# schematic.net
KiCad netlist of a schematic drawn in Altium Designer
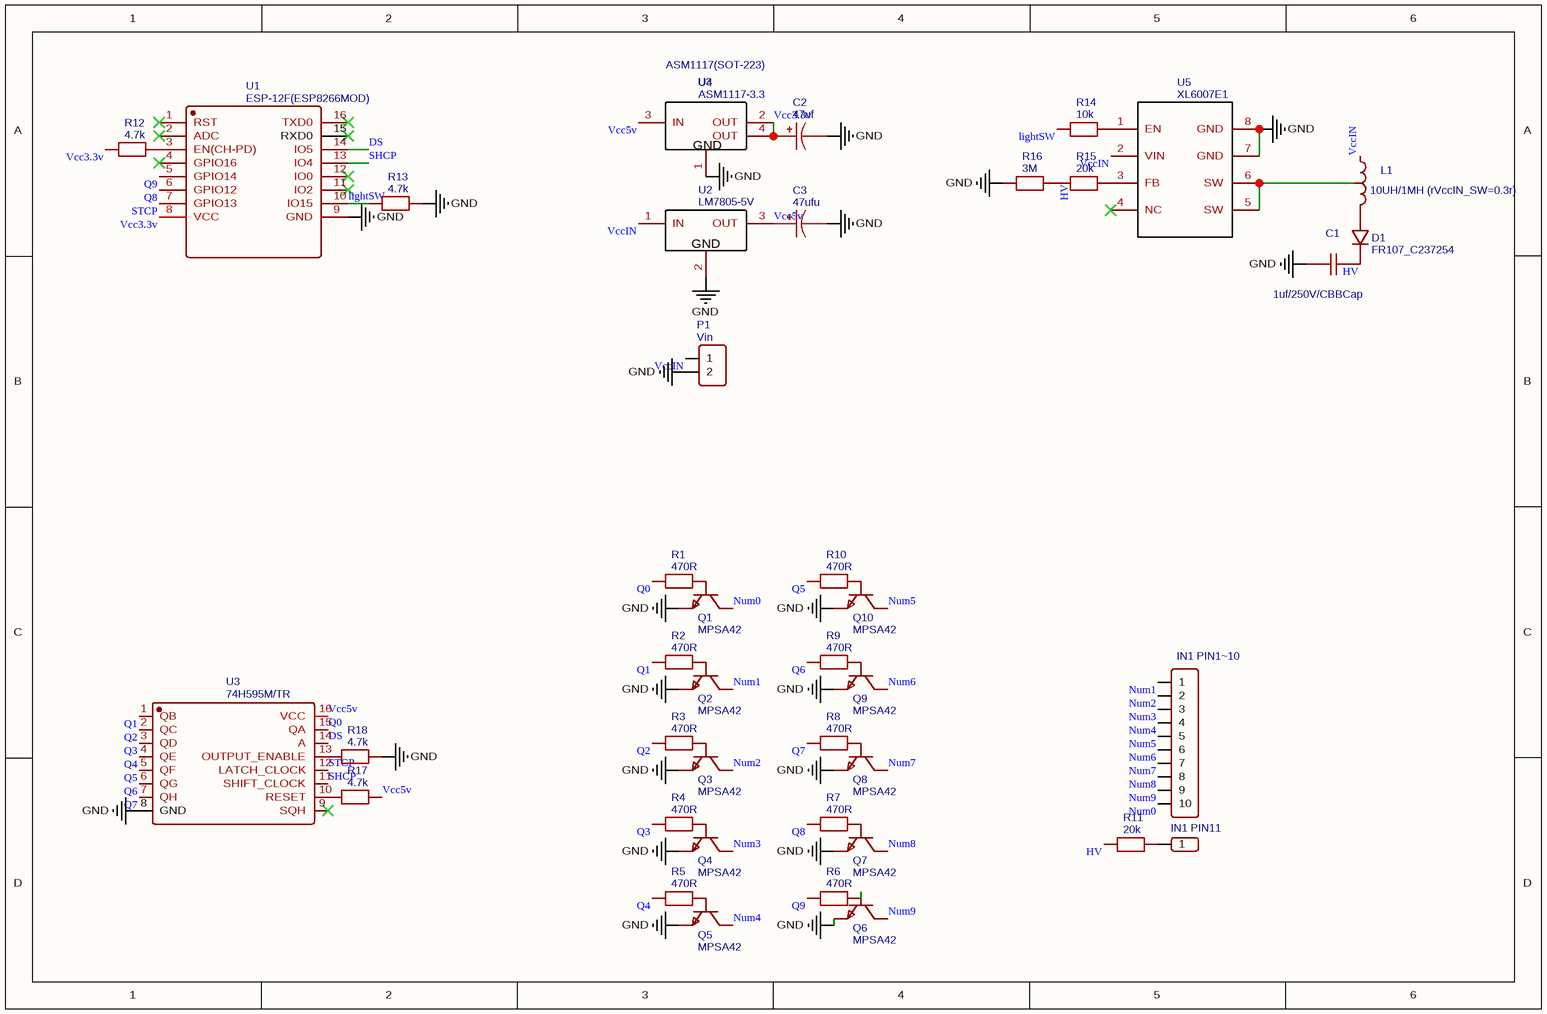
[diagram p0: schematic.schdoc]

(export (version "E")
  (design (tool "Eeschema 10.0.6"))
  (components
    (comp (ref "C1")
      (value "1uf/250V/CBBCap")
      (fields
        (field (name "BOM_SUPPLIER PART") "C29321")
        (field (name "BOM_MANUFACTURER PART") "1uf/250V/CBBCapacitor")
      )
      (libsource (lib "altium-import") (part "root_2_1uf/250V/CBBCap_"))
    )
    (comp (ref "C2")
      (value "47uf")
      (fields (field (name "CONTRIBUTOR") "LCEDA_Lib"))
      (libsource (lib "altium-import") (part "root_0_47uf_"))
    )
    (comp (ref "C3")
      (value "47ufu")
      (fields (field (name "CONTRIBUTOR") "LCEDA_Lib"))
      (libsource (lib "altium-import") (part "root_0_47ufu_"))
    )
    (comp (ref "D1")
      (value "FR107_C237254")
      (fields
        (field (name "BOM_SUPPLIER PART") "C237254")
        (field (name "BOM_MANUFACTURER PART") "FR107")
        (field (name "CONTRIBUTOR") "LCSC")
      )
      (libsource (lib "altium-import") (part "root_1_FR107_C237254_"))
    )
    (comp (ref "H1")
      (value "IN1 PIN1~10")
      (fields (field (name "BOM_SUPPLIER PART") "C35445") (field (name "CONTRIBUTOR") "LCEDA_Lib"))
      (libsource (lib "altium-import") (part "root_0_IN1 PIN1~10_"))
    )
    (comp (ref "J1")
      (value "IN1 PIN11")
      (fields (field (name "BOM_SUPPLIER PART") "C81276") (field (name "CONTRIBUTOR") "LCEDA_Lib"))
      (libsource (lib "altium-import") (part "root_0_IN1 PIN11_"))
    )
    (comp (ref "L1")
      (value "10UH/1MH (rVccIN_SW=0.3r)")
      (fields (field (name "CONTRIBUTOR") "NKB-NB"))
      (libsource (lib "altium-import") (part "root_0_10UH/1MH (rVccIN_SW=0.3r)_"))
    )
    (comp (ref "P1")
      (value "Vin")
      (fields (field (name "CONTRIBUTOR") "LCEDA_Lib"))
      (libsource (lib "altium-import") (part "root_0_Vin_"))
    )
    (comp (ref "Q1")
      (value "MPSA42")
      (fields (field (name "BOM_SUPPLIER PART") "C118557") (field (name "CONTRIBUTOR") "LCSC"))
      (libsource (lib "altium-import") (part "root_3_MPSA42_"))
    )
    (comp (ref "Q2")
      (value "MPSA42")
      (fields (field (name "BOM_SUPPLIER PART") "C118557") (field (name "CONTRIBUTOR") "LCSC"))
      (libsource (lib "altium-import") (part "root_3_MPSA42_"))
    )
    (comp (ref "Q3")
      (value "MPSA42")
      (fields (field (name "BOM_SUPPLIER PART") "C118557") (field (name "CONTRIBUTOR") "LCSC"))
      (libsource (lib "altium-import") (part "root_3_MPSA42_"))
    )
    (comp (ref "Q4")
      (value "MPSA42")
      (fields (field (name "BOM_SUPPLIER PART") "C118557") (field (name "CONTRIBUTOR") "LCSC"))
      (libsource (lib "altium-import") (part "root_3_MPSA42_"))
    )
    (comp (ref "Q5")
      (value "MPSA42")
      (fields (field (name "BOM_SUPPLIER PART") "C118557") (field (name "CONTRIBUTOR") "LCSC"))
      (libsource (lib "altium-import") (part "root_3_MPSA42_"))
    )
    (comp (ref "Q6")
      (value "MPSA42")
      (fields (field (name "BOM_SUPPLIER PART") "C118557") (field (name "CONTRIBUTOR") "LCSC"))
      (libsource (lib "altium-import") (part "root_3_MPSA42_"))
    )
    (comp (ref "Q7")
      (value "MPSA42")
      (fields (field (name "BOM_SUPPLIER PART") "C118557") (field (name "CONTRIBUTOR") "LCSC"))
      (libsource (lib "altium-import") (part "root_3_MPSA42_"))
    )
    (comp (ref "Q8")
      (value "MPSA42")
      (fields (field (name "BOM_SUPPLIER PART") "C118557") (field (name "CONTRIBUTOR") "LCSC"))
      (libsource (lib "altium-import") (part "root_3_MPSA42_"))
    )
    (comp (ref "Q9")
      (value "MPSA42")
      (fields (field (name "BOM_SUPPLIER PART") "C118557") (field (name "CONTRIBUTOR") "LCSC"))
      (libsource (lib "altium-import") (part "root_3_MPSA42_"))
    )
    (comp (ref "Q10")
      (value "MPSA42")
      (fields (field (name "BOM_SUPPLIER PART") "C118557") (field (name "CONTRIBUTOR") "LCSC"))
      (libsource (lib "altium-import") (part "root_3_MPSA42_"))
    )
    (comp (ref "R1")
      (value "470R")
      (fields (field (name "CONTRIBUTOR") "LCEDA_Lib"))
      (libsource (lib "altium-import") (part "root_2_470R_"))
    )
    (comp (ref "R2")
      (value "470R")
      (fields (field (name "CONTRIBUTOR") "LCEDA_Lib"))
      (libsource (lib "altium-import") (part "root_2_470R_"))
    )
    (comp (ref "R3")
      (value "470R")
      (fields (field (name "CONTRIBUTOR") "LCEDA_Lib"))
      (libsource (lib "altium-import") (part "root_2_470R_"))
    )
    (comp (ref "R4")
      (value "470R")
      (fields (field (name "CONTRIBUTOR") "LCEDA_Lib"))
      (libsource (lib "altium-import") (part "root_2_470R_"))
    )
    (comp (ref "R5")
      (value "470R")
      (fields (field (name "CONTRIBUTOR") "LCEDA_Lib"))
      (libsource (lib "altium-import") (part "root_2_470R_"))
    )
    (comp (ref "R6")
      (value "470R")
      (fields (field (name "CONTRIBUTOR") "LCEDA_Lib"))
      (libsource (lib "altium-import") (part "root_2_470R_"))
    )
    (comp (ref "R7")
      (value "470R")
      (fields (field (name "CONTRIBUTOR") "LCEDA_Lib"))
      (libsource (lib "altium-import") (part "root_2_470R_"))
    )
    (comp (ref "R8")
      (value "470R")
      (fields (field (name "CONTRIBUTOR") "LCEDA_Lib"))
      (libsource (lib "altium-import") (part "root_2_470R_"))
    )
    (comp (ref "R9")
      (value "470R")
      (fields (field (name "CONTRIBUTOR") "LCEDA_Lib"))
      (libsource (lib "altium-import") (part "root_2_470R_"))
    )
    (comp (ref "R10")
      (value "470R")
      (fields (field (name "CONTRIBUTOR") "LCEDA_Lib"))
      (libsource (lib "altium-import") (part "root_2_470R_"))
    )
    (comp (ref "R11")
      (value "20k")
      (fields (field (name "CONTRIBUTOR") "LCEDA_Lib"))
      (libsource (lib "altium-import") (part "root_0_20k_"))
    )
    (comp (ref "R12")
      (value "4.7k")
      (fields (field (name "CONTRIBUTOR") "LCEDA_Lib"))
      (libsource (lib "altium-import") (part "root_2_4.7k_"))
    )
    (comp (ref "R13")
      (value "4.7k")
      (fields (field (name "CONTRIBUTOR") "LCEDA_Lib"))
      (libsource (lib "altium-import") (part "root_0_4.7k_"))
    )
    (comp (ref "R14")
      (value "10k")
      (fields (field (name "CONTRIBUTOR") "LCEDA_Lib"))
      (libsource (lib "altium-import") (part "root_0_10k_"))
    )
    (comp (ref "R15")
      (value "20k")
      (fields (field (name "CONTRIBUTOR") "LCEDA_Lib"))
      (libsource (lib "altium-import") (part "root_0_20k_"))
    )
    (comp (ref "R16")
      (value "3M")
      (fields (field (name "CONTRIBUTOR") "LCEDA_Lib"))
      (libsource (lib "altium-import") (part "root_0_3M_"))
    )
    (comp (ref "R17")
      (value "4.7k")
      (fields (field (name "CONTRIBUTOR") "LCEDA_Lib"))
      (libsource (lib "altium-import") (part "root_0_4.7k_"))
    )
    (comp (ref "R18")
      (value "4.7k")
      (fields (field (name "CONTRIBUTOR") "LCEDA_Lib"))
      (libsource (lib "altium-import") (part "root_0_4.7k_"))
    )
    (comp (ref "U1")
      (value "ESP-12F(ESP8266MOD)")
      (fields (field (name "BOM_SUPPLIER PART") "C82891") (field (name "CONTRIBUTOR") "Diago"))
      (libsource (lib "altium-import") (part "root_0_ESP-12F(ESP8266MOD)_"))
    )
    (comp (ref "U2")
      (value "LM7805-5V")
      (fields (field (name "BOM_SUPPLIER PART") "C9900008050") (field (name "CONTRIBUTOR") "LCSC"))
      (libsource (lib "altium-import") (part "root_0_LM7805-5V_"))
    )
    (comp (ref "U3")
      (value "74H595M/TR")
      (fields (field (name "CONTRIBUTOR") "lianan"))
      (libsource (lib "altium-import") (part "root_0_74H595M/TR_"))
    )
    (comp (ref "U4")
      (value "ASM1117-3.3")
      (fields (field (name "CONTRIBUTOR") "shiznegjie"))
      (libsource (lib "altium-import") (part "root_0_ASM1117-3.3_"))
    )
    (comp (ref "U5")
      (value "XL6007E1")
      (fields (field (name "BOM_SUPPLIER PART") "C73334") (field (name "CONTRIBUTOR") "roco2022"))
      (libsource (lib "altium-import") (part "root_0_XL6007E1_"))
    )
  )
  (nets
    (net (code "1") (name "/DS") (class "Default")
      (node (ref "U1") (pin "14") (pinfunction "IO5_14") (pintype "passive"))
      (node (ref "U3") (pin "14") (pinfunction "A_14") (pintype "passive"))
    )
    (net (code "2") (name "/HV") (class "Default")
      (node (ref "C1") (pin "1") (pinfunction "1_1") (pintype "passive"))
      (node (ref "D1") (pin "1") (pinfunction "K_1") (pintype "passive"))
      (node (ref "R11") (pin "1") (pinfunction "1_1") (pintype "passive"))
      (node (ref "R15") (pin "1") (pinfunction "1_1") (pintype "passive"))
      (node (ref "R16") (pin "2") (pinfunction "2_2") (pintype "passive"))
    )
    (net (code "3") (name "/Num0") (class "Default")
      (node (ref "H1") (pin "10") (pinfunction "10_10") (pintype "passive"))
      (node (ref "Q1") (pin "3") (pinfunction "C_3") (pintype "passive"))
    )
    (net (code "4") (name "/Num1") (class "Default")
      (node (ref "H1") (pin "1") (pinfunction "1_1") (pintype "passive"))
      (node (ref "Q2") (pin "3") (pinfunction "C_3") (pintype "passive"))
    )
    (net (code "5") (name "/Num2") (class "Default")
      (node (ref "H1") (pin "2") (pinfunction "2_2") (pintype "passive"))
      (node (ref "Q3") (pin "3") (pinfunction "C_3") (pintype "passive"))
    )
    (net (code "6") (name "/Num3") (class "Default")
      (node (ref "H1") (pin "3") (pinfunction "3_3") (pintype "passive"))
      (node (ref "Q4") (pin "3") (pinfunction "C_3") (pintype "passive"))
    )
    (net (code "7") (name "/Num4") (class "Default")
      (node (ref "H1") (pin "4") (pinfunction "4_4") (pintype "passive"))
      (node (ref "Q5") (pin "3") (pinfunction "C_3") (pintype "passive"))
    )
    (net (code "8") (name "/Num5") (class "Default")
      (node (ref "H1") (pin "5") (pinfunction "5_5") (pintype "passive"))
      (node (ref "Q10") (pin "3") (pinfunction "C_3") (pintype "passive"))
    )
    (net (code "9") (name "/Num6") (class "Default")
      (node (ref "H1") (pin "6") (pinfunction "6_6") (pintype "passive"))
      (node (ref "Q9") (pin "3") (pinfunction "C_3") (pintype "passive"))
    )
    (net (code "10") (name "/Num7") (class "Default")
      (node (ref "H1") (pin "7") (pinfunction "7_7") (pintype "passive"))
      (node (ref "Q8") (pin "3") (pinfunction "C_3") (pintype "passive"))
    )
    (net (code "11") (name "/Num8") (class "Default")
      (node (ref "H1") (pin "8") (pinfunction "8_8") (pintype "passive"))
      (node (ref "Q7") (pin "3") (pinfunction "C_3") (pintype "passive"))
    )
    (net (code "12") (name "/Num9") (class "Default")
      (node (ref "H1") (pin "9") (pinfunction "9_9") (pintype "passive"))
      (node (ref "Q6") (pin "3") (pinfunction "C_3") (pintype "passive"))
    )
    (net (code "13") (name "/Q0") (class "Default")
      (node (ref "R1") (pin "2") (pinfunction "2_2") (pintype "passive"))
      (node (ref "U3") (pin "15") (pinfunction "QA_15") (pintype "passive"))
    )
    (net (code "14") (name "/Q1") (class "Default")
      (node (ref "R2") (pin "2") (pinfunction "2_2") (pintype "passive"))
      (node (ref "U3") (pin "1") (pinfunction "QB_1") (pintype "passive"))
    )
    (net (code "15") (name "/Q2") (class "Default")
      (node (ref "R3") (pin "2") (pinfunction "2_2") (pintype "passive"))
      (node (ref "U3") (pin "2") (pinfunction "QC_2") (pintype "passive"))
    )
    (net (code "16") (name "/Q3") (class "Default")
      (node (ref "R4") (pin "2") (pinfunction "2_2") (pintype "passive"))
      (node (ref "U3") (pin "3") (pinfunction "QD_3") (pintype "passive"))
    )
    (net (code "17") (name "/Q4") (class "Default")
      (node (ref "R5") (pin "2") (pinfunction "2_2") (pintype "passive"))
      (node (ref "U3") (pin "4") (pinfunction "QE_4") (pintype "passive"))
    )
    (net (code "18") (name "/Q5") (class "Default")
      (node (ref "R10") (pin "2") (pinfunction "2_2") (pintype "passive"))
      (node (ref "U3") (pin "5") (pinfunction "QF_5") (pintype "passive"))
    )
    (net (code "19") (name "/Q6") (class "Default")
      (node (ref "R9") (pin "2") (pinfunction "2_2") (pintype "passive"))
      (node (ref "U3") (pin "6") (pinfunction "QG_6") (pintype "passive"))
    )
    (net (code "20") (name "/Q7") (class "Default")
      (node (ref "R8") (pin "2") (pinfunction "2_2") (pintype "passive"))
      (node (ref "U3") (pin "7") (pinfunction "QH_7") (pintype "passive"))
    )
    (net (code "21") (name "/Q8") (class "Default")
      (node (ref "R7") (pin "2") (pinfunction "2_2") (pintype "passive"))
      (node (ref "U1") (pin "6") (pinfunction "GPIO12_6") (pintype "passive"))
    )
    (net (code "22") (name "/Q9") (class "Default")
      (node (ref "R6") (pin "2") (pinfunction "2_2") (pintype "passive"))
      (node (ref "U1") (pin "5") (pinfunction "GPIO14_5") (pintype "passive"))
    )
    (net (code "23") (name "/SHCP") (class "Default")
      (node (ref "U1") (pin "13") (pinfunction "IO4_13") (pintype "passive"))
      (node (ref "U3") (pin "11") (pinfunction "SHIFT_CLOCK_11") (pintype "passive"))
    )
    (net (code "24") (name "/STCP") (class "Default")
      (node (ref "U1") (pin "7") (pinfunction "GPIO13_7") (pintype "passive"))
      (node (ref "U3") (pin "12") (pinfunction "LATCH_CLOCK_12") (pintype "passive"))
    )
    (net (code "25") (name "/Vcc3.3v") (class "Default")
      (node (ref "C2") (pin "1") (pinfunction "1_1") (pintype "passive"))
      (node (ref "R12") (pin "2") (pinfunction "2_2") (pintype "passive"))
      (node (ref "U1") (pin "8") (pinfunction "VCC_8") (pintype "passive"))
      (node (ref "U4") (pin "2") (pinfunction "OUT_2") (pintype "passive"))
      (node (ref "U4") (pin "4") (pinfunction "OUT_4") (pintype "passive"))
    )
    (net (code "26") (name "/Vcc5v") (class "Default")
      (node (ref "C3") (pin "1") (pinfunction "1_1") (pintype "passive"))
      (node (ref "R17") (pin "2") (pinfunction "2_2") (pintype "passive"))
      (node (ref "U2") (pin "3") (pinfunction "OUT_3") (pintype "passive"))
      (node (ref "U3") (pin "16") (pinfunction "VCC_16") (pintype "passive"))
      (node (ref "U4") (pin "3") (pinfunction "IN_3") (pintype "passive"))
    )
    (net (code "27") (name "/VccIN") (class "Default")
      (node (ref "L1") (pin "3") (pinfunction "3_3") (pintype "passive"))
      (node (ref "P1") (pin "1") (pinfunction "1_1") (pintype "passive"))
      (node (ref "U2") (pin "1") (pinfunction "IN_1") (pintype "passive"))
      (node (ref "U5") (pin "2") (pinfunction "VIN_2") (pintype "passive"))
    )
    (net (code "28") (name "/lightSW") (class "Default")
      (node (ref "R13") (pin "1") (pinfunction "1_1") (pintype "passive"))
      (node (ref "R14") (pin "1") (pinfunction "1_1") (pintype "passive"))
      (node (ref "U1") (pin "10") (pinfunction "IO15_10") (pintype "passive"))
    )
    (net (code "29") (name "GND") (class "Default")
      (node (ref "C1") (pin "2") (pinfunction "2_2") (pintype "passive"))
      (node (ref "C2") (pin "2") (pinfunction "2_2") (pintype "passive"))
      (node (ref "C3") (pin "2") (pinfunction "2_2") (pintype "passive"))
      (node (ref "P1") (pin "2") (pinfunction "2_2") (pintype "passive"))
      (node (ref "Q1") (pin "1") (pinfunction "E_1") (pintype "passive"))
      (node (ref "Q10") (pin "1") (pinfunction "E_1") (pintype "passive"))
      (node (ref "Q2") (pin "1") (pinfunction "E_1") (pintype "passive"))
      (node (ref "Q3") (pin "1") (pinfunction "E_1") (pintype "passive"))
      (node (ref "Q4") (pin "1") (pinfunction "E_1") (pintype "passive"))
      (node (ref "Q5") (pin "1") (pinfunction "E_1") (pintype "passive"))
      (node (ref "Q6") (pin "1") (pinfunction "E_1") (pintype "passive"))
      (node (ref "Q7") (pin "1") (pinfunction "E_1") (pintype "passive"))
      (node (ref "Q8") (pin "1") (pinfunction "E_1") (pintype "passive"))
      (node (ref "Q9") (pin "1") (pinfunction "E_1") (pintype "passive"))
      (node (ref "R13") (pin "2") (pinfunction "2_2") (pintype "passive"))
      (node (ref "R16") (pin "1") (pinfunction "1_1") (pintype "passive"))
      (node (ref "R18") (pin "2") (pinfunction "2_2") (pintype "passive"))
      (node (ref "U1") (pin "9") (pinfunction "GND_9") (pintype "passive"))
      (node (ref "U2") (pin "2") (pinfunction "GND_2") (pintype "passive"))
      (node (ref "U3") (pin "8") (pinfunction "GND_8") (pintype "passive"))
      (node (ref "U4") (pin "1") (pinfunction "ADJ_1") (pintype "passive"))
      (node (ref "U5") (pin "7") (pinfunction "GND_7") (pintype "passive"))
      (node (ref "U5") (pin "8") (pinfunction "GND_8") (pintype "passive"))
    )
    (net (code "30") (name "Net-(D1-A)") (class "Default")
      (node (ref "D1") (pin "2") (pinfunction "A_2") (pintype "passive"))
      (node (ref "L1") (pin "2") (pinfunction "2_2") (pintype "passive"))
    )
    (net (code "31") (name "Net-(J1-Pad1)") (class "Default")
      (node (ref "J1") (pin "1") (pinfunction "1_1") (pintype "passive"))
      (node (ref "R11") (pin "2") (pinfunction "2_2") (pintype "passive"))
    )
    (net (code "32") (name "Net-(L1-Pad1)") (class "Default")
      (node (ref "L1") (pin "1") (pinfunction "1_1") (pintype "passive"))
      (node (ref "U5") (pin "5") (pinfunction "SW_5") (pintype "passive"))
      (node (ref "U5") (pin "6") (pinfunction "SW_6") (pintype "passive"))
    )
    (net (code "33") (name "Net-(Q1-B)") (class "Default")
      (node (ref "Q1") (pin "2") (pinfunction "B_2") (pintype "passive"))
      (node (ref "R1") (pin "1") (pinfunction "1_1") (pintype "passive"))
    )
    (net (code "34") (name "Net-(Q2-B)") (class "Default")
      (node (ref "Q2") (pin "2") (pinfunction "B_2") (pintype "passive"))
      (node (ref "R2") (pin "1") (pinfunction "1_1") (pintype "passive"))
    )
    (net (code "35") (name "Net-(Q3-B)") (class "Default")
      (node (ref "Q3") (pin "2") (pinfunction "B_2") (pintype "passive"))
      (node (ref "R3") (pin "1") (pinfunction "1_1") (pintype "passive"))
    )
    (net (code "36") (name "Net-(Q4-B)") (class "Default")
      (node (ref "Q4") (pin "2") (pinfunction "B_2") (pintype "passive"))
      (node (ref "R4") (pin "1") (pinfunction "1_1") (pintype "passive"))
    )
    (net (code "37") (name "Net-(Q5-B)") (class "Default")
      (node (ref "Q5") (pin "2") (pinfunction "B_2") (pintype "passive"))
      (node (ref "R5") (pin "1") (pinfunction "1_1") (pintype "passive"))
    )
    (net (code "38") (name "Net-(Q6-B)") (class "Default")
      (node (ref "Q6") (pin "2") (pinfunction "B_2") (pintype "passive"))
      (node (ref "R6") (pin "1") (pinfunction "1_1") (pintype "passive"))
    )
    (net (code "39") (name "Net-(Q7-B)") (class "Default")
      (node (ref "Q7") (pin "2") (pinfunction "B_2") (pintype "passive"))
      (node (ref "R7") (pin "1") (pinfunction "1_1") (pintype "passive"))
    )
    (net (code "40") (name "Net-(Q8-B)") (class "Default")
      (node (ref "Q8") (pin "2") (pinfunction "B_2") (pintype "passive"))
      (node (ref "R8") (pin "1") (pinfunction "1_1") (pintype "passive"))
    )
    (net (code "41") (name "Net-(Q9-B)") (class "Default")
      (node (ref "Q9") (pin "2") (pinfunction "B_2") (pintype "passive"))
      (node (ref "R9") (pin "1") (pinfunction "1_1") (pintype "passive"))
    )
    (net (code "42") (name "Net-(Q10-B)") (class "Default")
      (node (ref "Q10") (pin "2") (pinfunction "B_2") (pintype "passive"))
      (node (ref "R10") (pin "1") (pinfunction "1_1") (pintype "passive"))
    )
    (net (code "43") (name "Net-(U1-EN(CH-PD))") (class "Default")
      (node (ref "R12") (pin "1") (pinfunction "1_1") (pintype "passive"))
      (node (ref "U1") (pin "3") (pinfunction "EN(CH-PD)_3") (pintype "passive"))
    )
    (net (code "44") (name "Net-(U3-OUTPUT_ENABLE)") (class "Default")
      (node (ref "R18") (pin "1") (pinfunction "1_1") (pintype "passive"))
      (node (ref "U3") (pin "13") (pinfunction "OUTPUT_ENABLE_13") (pintype "passive"))
    )
    (net (code "45") (name "Net-(U3-RESET)") (class "Default")
      (node (ref "R17") (pin "1") (pinfunction "1_1") (pintype "passive"))
      (node (ref "U3") (pin "10") (pinfunction "RESET_10") (pintype "passive"))
    )
    (net (code "46") (name "Net-(U5-EN)") (class "Default")
      (node (ref "R14") (pin "2") (pinfunction "2_2") (pintype "passive"))
      (node (ref "U5") (pin "1") (pinfunction "EN_1") (pintype "passive"))
    )
    (net (code "47") (name "Net-(U5-FB)") (class "Default")
      (node (ref "R15") (pin "2") (pinfunction "2_2") (pintype "passive"))
      (node (ref "U5") (pin "3") (pinfunction "FB_3") (pintype "passive"))
    )
    (net (code "48") (name "unconnected-(U1-ADC-Pad2)") (class "Default")
      (node (ref "U1") (pin "2") (pinfunction "ADC_2") (pintype "passive+no_connect"))
    )
    (net (code "49") (name "unconnected-(U1-GPIO16-Pad4)") (class "Default")
      (node (ref "U1") (pin "4") (pinfunction "GPIO16_4") (pintype "passive+no_connect"))
    )
    (net (code "50") (name "unconnected-(U1-IO0-Pad12)") (class "Default")
      (node (ref "U1") (pin "12") (pinfunction "IO0_12") (pintype "passive+no_connect"))
    )
    (net (code "51") (name "unconnected-(U1-IO2-Pad11)") (class "Default")
      (node (ref "U1") (pin "11") (pinfunction "IO2_11") (pintype "passive+no_connect"))
    )
    (net (code "52") (name "unconnected-(U1-RST-Pad1)") (class "Default")
      (node (ref "U1") (pin "1") (pinfunction "RST_1") (pintype "passive+no_connect"))
    )
    (net (code "53") (name "unconnected-(U1-RXD0-Pad15)") (class "Default")
      (node (ref "U1") (pin "15") (pinfunction "RXD0_15") (pintype "passive+no_connect"))
    )
    (net (code "54") (name "unconnected-(U1-TXD0-Pad16)") (class "Default")
      (node (ref "U1") (pin "16") (pinfunction "TXD0_16") (pintype "passive+no_connect"))
    )
    (net (code "55") (name "unconnected-(U3-SQH-Pad9)") (class "Default")
      (node (ref "U3") (pin "9") (pinfunction "SQH_9") (pintype "passive+no_connect"))
    )
    (net (code "56") (name "unconnected-(U5-NC-Pad4)") (class "Default")
      (node (ref "U5") (pin "4") (pinfunction "NC_4") (pintype "passive+no_connect"))
    )
  )
)
